# gpio.net
KiCad netlist of a schematic drawn in Altium Designer
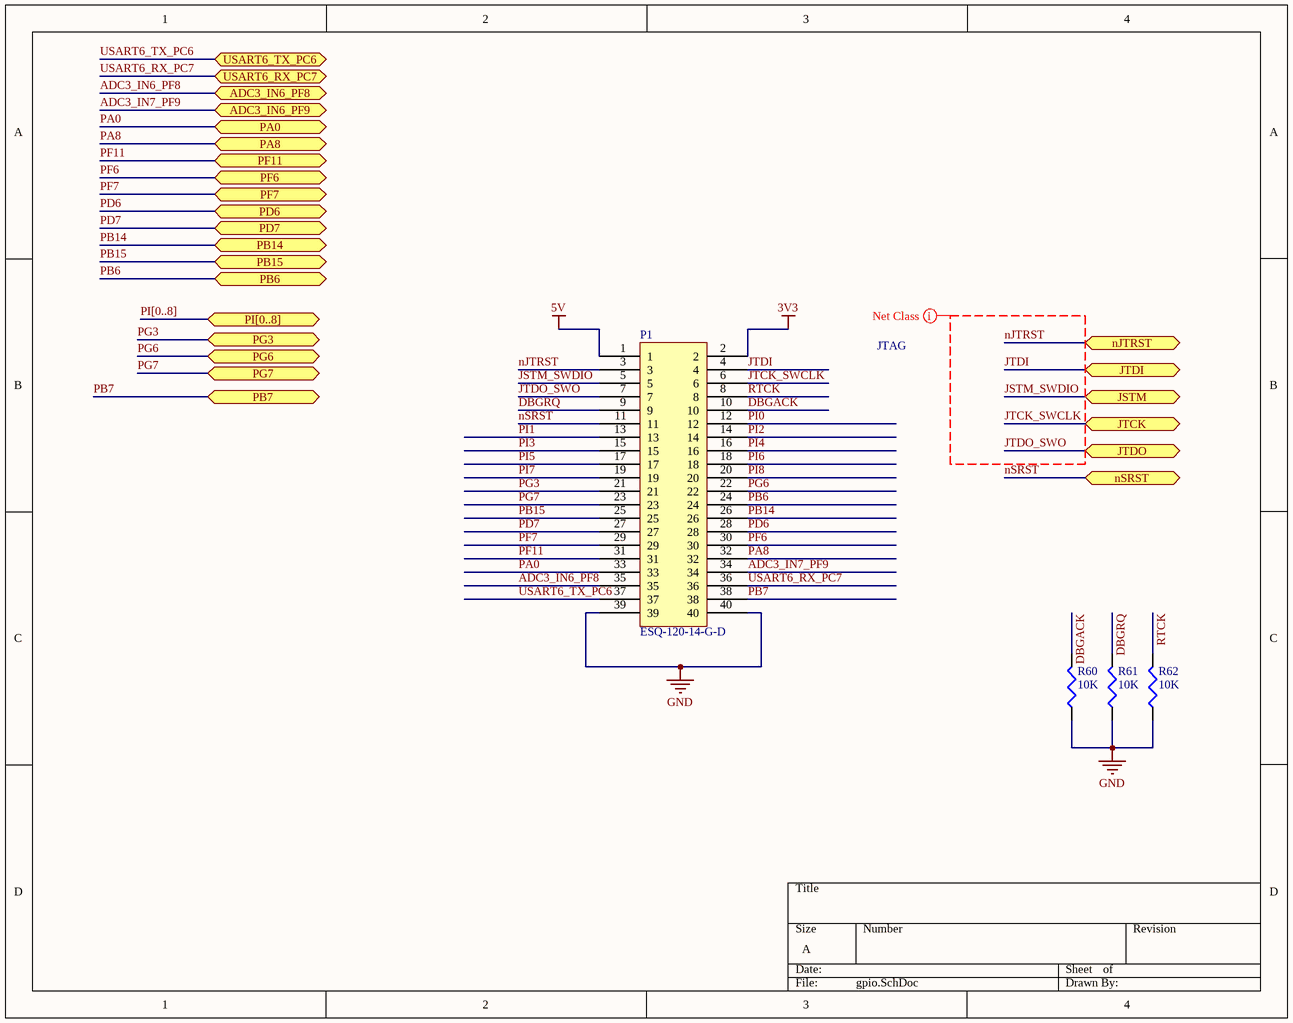
[diagram p0: gpio.SchDoc]

(export (version "E")
  (design (tool "Eeschema 10.0.6"))
  (components
    (comp (ref "P1")
      (value "ESQ-120-14-G-D")
      (footprint "PBD40")
      (description "CONN RCPT 40POS .100\" DUAL GOLD")
      (fields
        (field (name "MANUFACTURER") "Samtec Inc.")
        (field (name ".CREATOR") "MM")
        (field (name ".CHECKED PCB") "MM")
        (field (name ".CHECKED SCH") "MM")
      )
      (libsource (lib "PinHead") (part "ESQ-120-14-G-D"))
    )
    (comp (ref "R60")
      (value "10K")
      (footprint "R0402")
      (description "RES 100 OHM 1/16W 1% 0402 SMD")
      (fields
        (field (name "MANUFACTURER") "Yageo")
        (field (name "MANUFACTURER PART NUMBER") "RC0402FR-07100RL")
        (field (name ".CHECKED PCB") "RF")
        (field (name ".CHECKED SCH") "RF")
      )
      (libsource (lib "iMX6_Rex_Development_Baseboard_V1I1") (part "RC0402FR-07100RL"))
    )
    (comp (ref "R61")
      (value "10K")
      (footprint "R0402")
      (description "RES 100 OHM 1/16W 1% 0402 SMD")
      (fields
        (field (name "MANUFACTURER") "Yageo")
        (field (name "MANUFACTURER PART NUMBER") "RC0402FR-07100RL")
        (field (name ".CHECKED PCB") "RF")
        (field (name ".CHECKED SCH") "RF")
      )
      (libsource (lib "iMX6_Rex_Development_Baseboard_V1I1") (part "RC0402FR-07100RL"))
    )
    (comp (ref "R62")
      (value "10K")
      (footprint "R0402")
      (description "RES 100 OHM 1/16W 1% 0402 SMD")
      (fields
        (field (name "MANUFACTURER") "Yageo")
        (field (name "MANUFACTURER PART NUMBER") "RC0402FR-07100RL")
        (field (name ".CHECKED PCB") "RF")
        (field (name ".CHECKED SCH") "RF")
      )
      (libsource (lib "iMX6_Rex_Development_Baseboard_V1I1") (part "RC0402FR-07100RL"))
    )
  )
  (nets
    (net (code "1") (name "/ADC3_IN6_PF8") (class "Default")
      (node (ref "P1") (pin "35") (pinfunction "35_35") (pintype "passive"))
    )
    (net (code "2") (name "/ADC3_IN7_PF9") (class "Default")
      (node (ref "P1") (pin "34") (pinfunction "34_34") (pintype "passive"))
    )
    (net (code "3") (name "/DBGACK") (class "Default")
      (node (ref "P1") (pin "10") (pinfunction "10_10") (pintype "passive"))
      (node (ref "R60") (pin "2") (pinfunction "2_2") (pintype "passive"))
    )
    (net (code "4") (name "/DBGRQ") (class "Default")
      (node (ref "P1") (pin "9") (pinfunction "9_9") (pintype "passive"))
      (node (ref "R61") (pin "2") (pinfunction "2_2") (pintype "passive"))
    )
    (net (code "5") (name "/JSTM_SWDIO") (class "Default")
      (node (ref "P1") (pin "5") (pinfunction "5_5") (pintype "passive"))
    )
    (net (code "6") (name "/JTCK_SWCLK") (class "Default")
      (node (ref "P1") (pin "6") (pinfunction "6_6") (pintype "passive"))
    )
    (net (code "7") (name "/JTDI") (class "Default")
      (node (ref "P1") (pin "4") (pinfunction "4_4") (pintype "passive"))
    )
    (net (code "8") (name "/JTDO_SWO") (class "Default")
      (node (ref "P1") (pin "7") (pinfunction "7_7") (pintype "passive"))
    )
    (net (code "9") (name "/PA0") (class "Default")
      (node (ref "P1") (pin "33") (pinfunction "33_33") (pintype "passive"))
    )
    (net (code "10") (name "/PA8") (class "Default")
      (node (ref "P1") (pin "32") (pinfunction "32_32") (pintype "passive"))
    )
    (net (code "11") (name "/PB6") (class "Default")
      (node (ref "P1") (pin "24") (pinfunction "24_24") (pintype "passive"))
    )
    (net (code "12") (name "/PB7") (class "Default")
      (node (ref "P1") (pin "38") (pinfunction "38_38") (pintype "passive"))
    )
    (net (code "13") (name "/PB14") (class "Default")
      (node (ref "P1") (pin "26") (pinfunction "26_26") (pintype "passive"))
    )
    (net (code "14") (name "/PB15") (class "Default")
      (node (ref "P1") (pin "25") (pinfunction "25_25") (pintype "passive"))
    )
    (net (code "15") (name "/PD6") (class "Default")
      (node (ref "P1") (pin "28") (pinfunction "28_28") (pintype "passive"))
    )
    (net (code "16") (name "/PD7") (class "Default")
      (node (ref "P1") (pin "27") (pinfunction "27_27") (pintype "passive"))
    )
    (net (code "17") (name "/PF6") (class "Default")
      (node (ref "P1") (pin "30") (pinfunction "30_30") (pintype "passive"))
    )
    (net (code "18") (name "/PF7") (class "Default")
      (node (ref "P1") (pin "29") (pinfunction "29_29") (pintype "passive"))
    )
    (net (code "19") (name "/PF11") (class "Default")
      (node (ref "P1") (pin "31") (pinfunction "31_31") (pintype "passive"))
    )
    (net (code "20") (name "/PG3") (class "Default")
      (node (ref "P1") (pin "21") (pinfunction "21_21") (pintype "passive"))
    )
    (net (code "21") (name "/PG6") (class "Default")
      (node (ref "P1") (pin "22") (pinfunction "22_22") (pintype "passive"))
    )
    (net (code "22") (name "/PG7") (class "Default")
      (node (ref "P1") (pin "23") (pinfunction "23_23") (pintype "passive"))
    )
    (net (code "23") (name "/PI0") (class "Default")
      (node (ref "P1") (pin "12") (pinfunction "12_12") (pintype "passive"))
    )
    (net (code "24") (name "/PI1") (class "Default")
      (node (ref "P1") (pin "13") (pinfunction "13_13") (pintype "passive"))
    )
    (net (code "25") (name "/PI2") (class "Default")
      (node (ref "P1") (pin "14") (pinfunction "14_14") (pintype "passive"))
    )
    (net (code "26") (name "/PI3") (class "Default")
      (node (ref "P1") (pin "15") (pinfunction "15_15") (pintype "passive"))
    )
    (net (code "27") (name "/PI4") (class "Default")
      (node (ref "P1") (pin "16") (pinfunction "16_16") (pintype "passive"))
    )
    (net (code "28") (name "/PI5") (class "Default")
      (node (ref "P1") (pin "17") (pinfunction "17_17") (pintype "passive"))
    )
    (net (code "29") (name "/PI6") (class "Default")
      (node (ref "P1") (pin "18") (pinfunction "18_18") (pintype "passive"))
    )
    (net (code "30") (name "/PI7") (class "Default")
      (node (ref "P1") (pin "19") (pinfunction "19_19") (pintype "passive"))
    )
    (net (code "31") (name "/PI8") (class "Default")
      (node (ref "P1") (pin "20") (pinfunction "20_20") (pintype "passive"))
    )
    (net (code "33") (name "/RTCK") (class "Default")
      (node (ref "P1") (pin "8") (pinfunction "8_8") (pintype "passive"))
      (node (ref "R62") (pin "2") (pinfunction "2_2") (pintype "passive"))
    )
    (net (code "34") (name "/USART6_RX_PC7") (class "Default")
      (node (ref "P1") (pin "36") (pinfunction "36_36") (pintype "passive"))
    )
    (net (code "35") (name "/USART6_TX_PC6") (class "Default")
      (node (ref "P1") (pin "37") (pinfunction "37_37") (pintype "passive"))
    )
    (net (code "36") (name "/nJTRST") (class "Default")
      (node (ref "P1") (pin "3") (pinfunction "3_3") (pintype "passive"))
    )
    (net (code "37") (name "/nSRST") (class "Default")
      (node (ref "P1") (pin "11") (pinfunction "11_11") (pintype "passive"))
    )
    (net (code "38") (name "3V3") (class "Default")
      (node (ref "P1") (pin "2") (pinfunction "2_2") (pintype "passive"))
    )
    (net (code "39") (name "5V") (class "Default")
      (node (ref "P1") (pin "1") (pinfunction "1_1") (pintype "passive"))
    )
    (net (code "40") (name "GND") (class "Default")
      (node (ref "P1") (pin "39") (pinfunction "39_39") (pintype "passive"))
      (node (ref "P1") (pin "40") (pinfunction "40_40") (pintype "passive"))
      (node (ref "R60") (pin "1") (pinfunction "1_1") (pintype "passive"))
      (node (ref "R61") (pin "1") (pinfunction "1_1") (pintype "passive"))
      (node (ref "R62") (pin "1") (pinfunction "1_1") (pintype "passive"))
    )
  )
)
